# Transceivers.net
KiCad netlist of a schematic drawn in Altium Designer
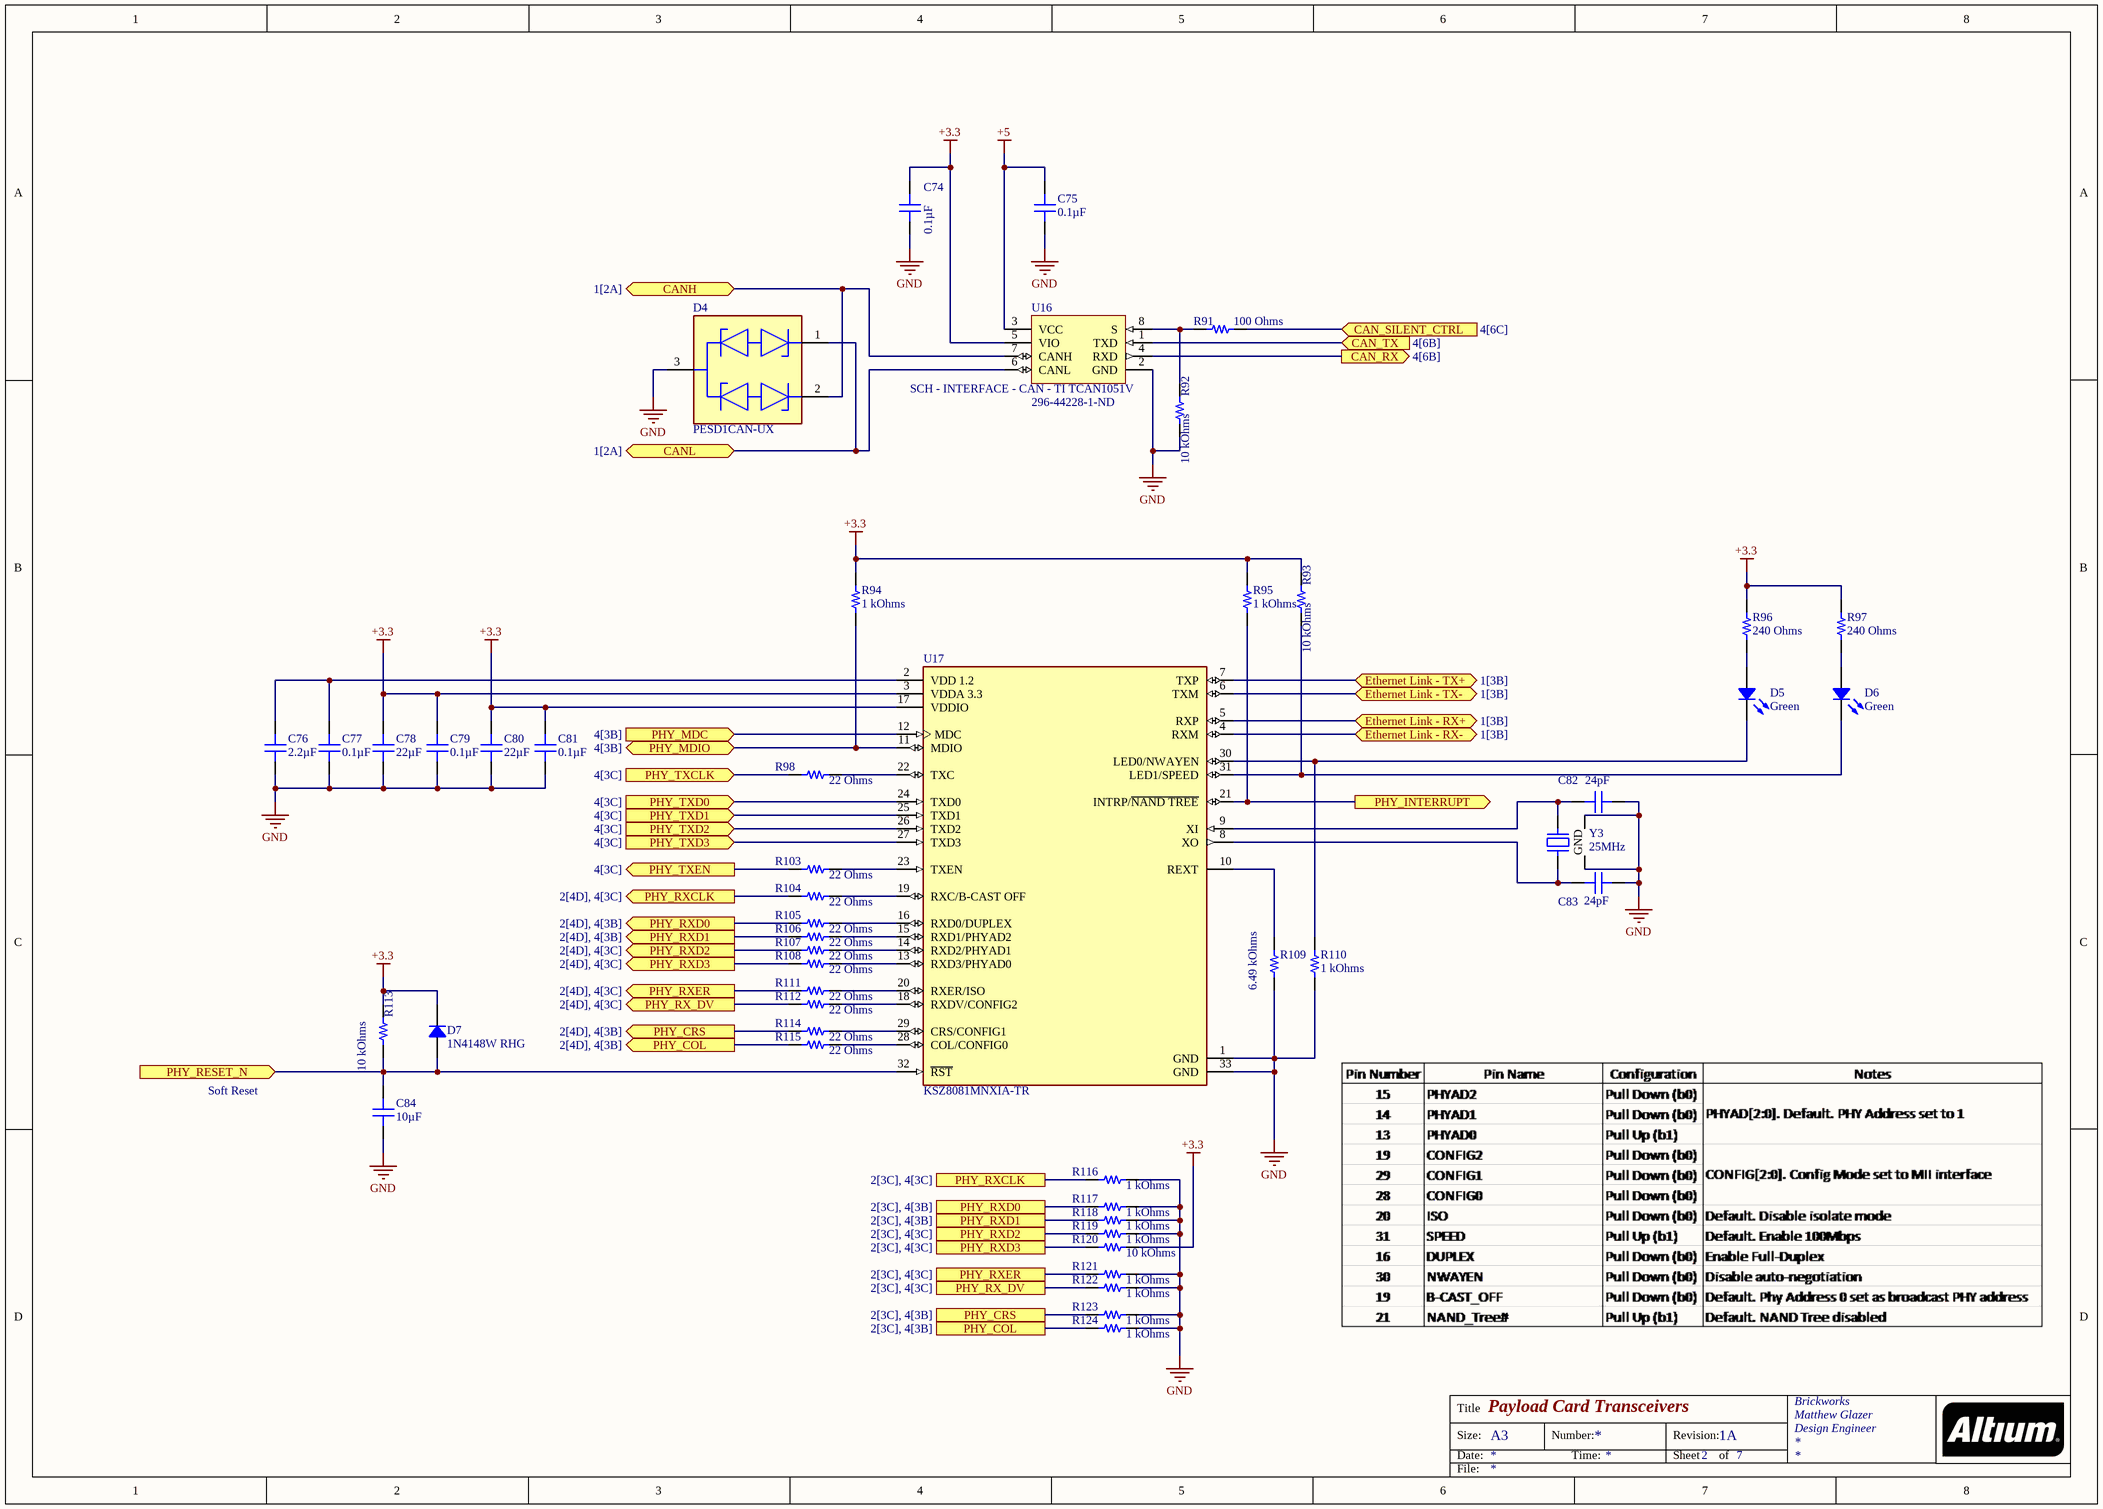
[diagram p0: Transceivers.SchDoc]

(export (version "E")
  (design (tool "Eeschema 10.0.6"))
  (components
    (comp (ref "C74")
      (value "0.1µF")
      (footprint "CAP 0603_1608")
      (description "CAP CER 0.1UF 25V X7R 0603")
      (fields
        (field (name "PART NUMBER") "CL10B104KA8WPNC")
        (field (name "MANUFACTURER") "Samsung Electro-Mechanics")
      )
      (libsource (lib "Celestial Altium Library - altium_library") (part "Capacitor"))
    )
    (comp (ref "C75")
      (value "0.1µF")
      (footprint "CAP 0603_1608")
      (description "CAP CER 0.1UF 25V X7R 0603")
      (fields
        (field (name "PART NUMBER") "CL10B104KA8WPNC")
        (field (name "MANUFACTURER") "Samsung Electro-Mechanics")
      )
      (libsource (lib "Celestial Altium Library - altium_library") (part "Capacitor"))
    )
    (comp (ref "C76")
      (value "2.2µF")
      (footprint "CAP 0805_2012")
      (description "CAP CER 2.2UF 10V X5R 0805")
      (fields
        (field (name "PART NUMBER") "CL21A225KPFNNNE")
        (field (name "MANUFACTURER") "Samsung Electro-Mechanics")
      )
      (libsource (lib "Celestial Altium Library - altium_library") (part "Capacitor"))
    )
    (comp (ref "C77")
      (value "0.1µF")
      (footprint "CAP 0603_1608")
      (description "CAP CER 0.1UF 25V X7R 0603")
      (fields
        (field (name "PART NUMBER") "CL10B104KA8WPNC")
        (field (name "MANUFACTURER") "Samsung Electro-Mechanics")
      )
      (libsource (lib "Celestial Altium Library - altium_library") (part "Capacitor"))
    )
    (comp (ref "C78")
      (value "22µF")
      (footprint "CAP 0805_2012")
      (description "CAP CER 22UF 10V X5R 0805")
      (fields
        (field (name "PART NUMBER") "CL21A226KPCLRNC")
        (field (name "MANUFACTURER") "Samsung Electro-Mechanics")
      )
      (libsource (lib "Celestial Altium Library - altium_library") (part "Capacitor"))
    )
    (comp (ref "C79")
      (value "0.1µF")
      (footprint "CAP 0603_1608")
      (description "CAP CER 0.1UF 25V X7R 0603")
      (fields
        (field (name "PART NUMBER") "CL10B104KA8WPNC")
        (field (name "MANUFACTURER") "Samsung Electro-Mechanics")
      )
      (libsource (lib "Celestial Altium Library - altium_library") (part "Capacitor"))
    )
    (comp (ref "C80")
      (value "22µF")
      (footprint "CAP 0805_2012")
      (description "CAP CER 22UF 10V X5R 0805")
      (fields
        (field (name "PART NUMBER") "CL21A226KPCLRNC")
        (field (name "MANUFACTURER") "Samsung Electro-Mechanics")
      )
      (libsource (lib "Celestial Altium Library - altium_library") (part "Capacitor"))
    )
    (comp (ref "C81")
      (value "0.1µF")
      (footprint "CAP 0603_1608")
      (description "CAP CER 0.1UF 25V X7R 0603")
      (fields
        (field (name "PART NUMBER") "CL10B104KA8WPNC")
        (field (name "MANUFACTURER") "Samsung Electro-Mechanics")
      )
      (libsource (lib "Celestial Altium Library - altium_library") (part "Capacitor"))
    )
    (comp (ref "C82")
      (value "24pF")
      (footprint "CAP 0603_1608")
      (description "CAP CER 24PF 50V C0G/NP0 0603")
      (fields
        (field (name "PART NUMBER") "CL10C240JB8NNNC")
        (field (name "MANUFACTURER") "Samsung Electro-Mechanics")
      )
      (libsource (lib "Celestial Altium Library - altium_library") (part "Capacitor"))
    )
    (comp (ref "C83")
      (value "24pF")
      (footprint "CAP 0603_1608")
      (description "CAP CER 24PF 50V C0G/NP0 0603")
      (fields
        (field (name "PART NUMBER") "CL10C240JB8NNNC")
        (field (name "MANUFACTURER") "Samsung Electro-Mechanics")
      )
      (libsource (lib "Celestial Altium Library - altium_library") (part "Capacitor"))
    )
    (comp (ref "C84")
      (value "10µF")
      (footprint "CAP 0805_2012")
      (description "CAP CER 10UF 16V X5R 0805")
      (fields (field (name "PART NUMBER") "CC0805KKX5R7BB106") (field (name "MANUFACTURER") "Yageo"))
      (libsource (lib "Celestial Altium Library - altium_library") (part "Capacitor"))
    )
    (comp (ref "D4")
      (value "PESD1CAN-UX")
      (footprint "FP-SOT323-MFG")
      (description "TVS DIODE 24V 50V SC70-3")
      (libsource (lib "Altium Content Vault") (part "04d57993b6b7b0f5b3c95ba4f97dea0"))
    )
    (comp (ref "D5")
      (value "Green")
      (footprint "LED 0603_1608 GREEN")
      (description "LED GREEN CLEAR CHIP SMD")
      (fields (field (name "PART NUMBER") "LTST-C193KGKT-5A") (field (name "MANUFACTURER") "Lite-On Inc."))
      (libsource (lib "Celestial Altium Library - altium_library") (part "LED"))
    )
    (comp (ref "D6")
      (value "Green")
      (footprint "LED 0603_1608 GREEN")
      (description "LED GREEN CLEAR CHIP SMD")
      (fields (field (name "PART NUMBER") "LTST-C193KGKT-5A") (field (name "MANUFACTURER") "Lite-On Inc."))
      (libsource (lib "Celestial Altium Library - altium_library") (part "LED"))
    )
    (comp (ref "D7")
      (value "1N4148W RHG")
      (footprint "SOD123F")
      (description "DIODE GEN PURP 100V 150MA SOD123")
      (fields (field (name "MANUFACTURER") "Taiwan Semiconductor Corporation"))
      (libsource (lib "Celestial Altium Library - altium_library") (part "Diode"))
    )
    (comp (ref "R91")
      (value "100 Ohms")
      (footprint "RES 0603_1608")
      (description "RES 100 OHM 1% 1/10W 0603")
      (fields
        (field (name "PART NUMBER") "RMCF0603FG100R")
        (field (name "MANUFACTURER") "Stackpole Electronics Inc")
      )
      (libsource (lib "Celestial Altium Library - altium_library") (part "Resistor"))
    )
    (comp (ref "R92")
      (value "10 kOhms")
      (footprint "RES 0603_1608")
      (description "RES 10K OHM 5% 1/10W 0603")
      (fields
        (field (name "PART NUMBER") "RMCF0603JT10K0")
        (field (name "MANUFACTURER") "Stackpole Electronics Inc")
      )
      (libsource (lib "Celestial Altium Library - altium_library") (part "Resistor"))
    )
    (comp (ref "R93")
      (value "10 kOhms")
      (footprint "RES 0603_1608")
      (description "RES 10K OHM 5% 1/10W 0603")
      (fields
        (field (name "PART NUMBER") "RMCF0603JT10K0")
        (field (name "MANUFACTURER") "Stackpole Electronics Inc")
      )
      (libsource (lib "Celestial Altium Library - altium_library") (part "Resistor"))
    )
    (comp (ref "R94")
      (value "1 kOhms")
      (footprint "RES 0603_1608")
      (description "RES 1K OHM 1% 1/8W 0603")
      (fields
        (field (name "PART NUMBER") "RNCP0603FTD1K00")
        (field (name "MANUFACTURER") "Stackpole Electronics Inc")
      )
      (libsource (lib "Celestial Altium Library - altium_library") (part "Resistor"))
    )
    (comp (ref "R95")
      (value "1 kOhms")
      (footprint "RES 0603_1608")
      (description "RES 1K OHM 1% 1/8W 0603")
      (fields
        (field (name "PART NUMBER") "RNCP0603FTD1K00")
        (field (name "MANUFACTURER") "Stackpole Electronics Inc")
      )
      (libsource (lib "Celestial Altium Library - altium_library") (part "Resistor"))
    )
    (comp (ref "R96")
      (value "240 Ohms")
      (footprint "RES 0603_1608")
      (description "RES 240 OHM 5% 1/10W 0603")
      (fields
        (field (name "PART NUMBER") "RMCF0603JT240R")
        (field (name "MANUFACTURER") "Stackpole Electronics Inc")
      )
      (libsource (lib "Celestial Altium Library - altium_library") (part "Resistor"))
    )
    (comp (ref "R97")
      (value "240 Ohms")
      (footprint "RES 0603_1608")
      (description "RES 240 OHM 5% 1/10W 0603")
      (fields
        (field (name "PART NUMBER") "RMCF0603JT240R")
        (field (name "MANUFACTURER") "Stackpole Electronics Inc")
      )
      (libsource (lib "Celestial Altium Library - altium_library") (part "Resistor"))
    )
    (comp (ref "R98")
      (value "22 Ohms")
      (footprint "RES 0603_1608")
      (description "RES 22 OHM 1% 1/10W 0603")
      (fields
        (field (name "PART NUMBER") "RMCF0603FT22R0")
        (field (name "MANUFACTURER") "Stackpole Electronics Inc")
      )
      (libsource (lib "Celestial Altium Library - altium_library") (part "Resistor"))
    )
    (comp (ref "R103")
      (value "22 Ohms")
      (footprint "RES 0603_1608")
      (description "RES 22 OHM 1% 1/10W 0603")
      (fields
        (field (name "PART NUMBER") "RMCF0603FT22R0")
        (field (name "MANUFACTURER") "Stackpole Electronics Inc")
      )
      (libsource (lib "Celestial Altium Library - altium_library") (part "Resistor"))
    )
    (comp (ref "R104")
      (value "22 Ohms")
      (footprint "RES 0603_1608")
      (description "RES 22 OHM 1% 1/10W 0603")
      (fields
        (field (name "PART NUMBER") "RMCF0603FT22R0")
        (field (name "MANUFACTURER") "Stackpole Electronics Inc")
      )
      (libsource (lib "Celestial Altium Library - altium_library") (part "Resistor"))
    )
    (comp (ref "R105")
      (value "22 Ohms")
      (footprint "RES 0603_1608")
      (description "RES 22 OHM 1% 1/10W 0603")
      (fields
        (field (name "PART NUMBER") "RMCF0603FT22R0")
        (field (name "MANUFACTURER") "Stackpole Electronics Inc")
      )
      (libsource (lib "Celestial Altium Library - altium_library") (part "Resistor"))
    )
    (comp (ref "R106")
      (value "22 Ohms")
      (footprint "RES 0603_1608")
      (description "RES 22 OHM 1% 1/10W 0603")
      (fields
        (field (name "PART NUMBER") "RMCF0603FT22R0")
        (field (name "MANUFACTURER") "Stackpole Electronics Inc")
      )
      (libsource (lib "Celestial Altium Library - altium_library") (part "Resistor"))
    )
    (comp (ref "R107")
      (value "22 Ohms")
      (footprint "RES 0603_1608")
      (description "RES 22 OHM 1% 1/10W 0603")
      (fields
        (field (name "PART NUMBER") "RMCF0603FT22R0")
        (field (name "MANUFACTURER") "Stackpole Electronics Inc")
      )
      (libsource (lib "Celestial Altium Library - altium_library") (part "Resistor"))
    )
    (comp (ref "R108")
      (value "22 Ohms")
      (footprint "RES 0603_1608")
      (description "RES 22 OHM 1% 1/10W 0603")
      (fields
        (field (name "PART NUMBER") "RMCF0603FT22R0")
        (field (name "MANUFACTURER") "Stackpole Electronics Inc")
      )
      (libsource (lib "Celestial Altium Library - altium_library") (part "Resistor"))
    )
    (comp (ref "R109")
      (value "6.49 kOhms")
      (footprint "RES 0603_1608")
      (description "RES 6.49K OHM 1% 1/8W 0603")
      (fields
        (field (name "PART NUMBER") "RNCP0603FTD6K49")
        (field (name "MANUFACTURER") "Stackpole Electronics Inc")
      )
      (libsource (lib "Celestial Altium Library - altium_library") (part "Resistor"))
    )
    (comp (ref "R110")
      (value "1 kOhms")
      (footprint "RES 0603_1608")
      (description "RES 1K OHM 1% 1/8W 0603")
      (fields
        (field (name "PART NUMBER") "RNCP0603FTD1K00")
        (field (name "MANUFACTURER") "Stackpole Electronics Inc")
      )
      (libsource (lib "Celestial Altium Library - altium_library") (part "Resistor"))
    )
    (comp (ref "R111")
      (value "22 Ohms")
      (footprint "RES 0603_1608")
      (description "RES 22 OHM 1% 1/10W 0603")
      (fields
        (field (name "PART NUMBER") "RMCF0603FT22R0")
        (field (name "MANUFACTURER") "Stackpole Electronics Inc")
      )
      (libsource (lib "Celestial Altium Library - altium_library") (part "Resistor"))
    )
    (comp (ref "R112")
      (value "22 Ohms")
      (footprint "RES 0603_1608")
      (description "RES 22 OHM 1% 1/10W 0603")
      (fields
        (field (name "PART NUMBER") "RMCF0603FT22R0")
        (field (name "MANUFACTURER") "Stackpole Electronics Inc")
      )
      (libsource (lib "Celestial Altium Library - altium_library") (part "Resistor"))
    )
    (comp (ref "R113")
      (value "10 kOhms")
      (footprint "RES 0603_1608")
      (description "RES 10K OHM 5% 1/10W 0603")
      (fields
        (field (name "PART NUMBER") "RMCF0603JT10K0")
        (field (name "MANUFACTURER") "Stackpole Electronics Inc")
      )
      (libsource (lib "Celestial Altium Library - altium_library") (part "Resistor"))
    )
    (comp (ref "R114")
      (value "22 Ohms")
      (footprint "RES 0603_1608")
      (description "RES 22 OHM 1% 1/10W 0603")
      (fields
        (field (name "PART NUMBER") "RMCF0603FT22R0")
        (field (name "MANUFACTURER") "Stackpole Electronics Inc")
      )
      (libsource (lib "Celestial Altium Library - altium_library") (part "Resistor"))
    )
    (comp (ref "R115")
      (value "22 Ohms")
      (footprint "RES 0603_1608")
      (description "RES 22 OHM 1% 1/10W 0603")
      (fields
        (field (name "PART NUMBER") "RMCF0603FT22R0")
        (field (name "MANUFACTURER") "Stackpole Electronics Inc")
      )
      (libsource (lib "Celestial Altium Library - altium_library") (part "Resistor"))
    )
    (comp (ref "R116")
      (value "1 kOhms")
      (footprint "RES 0603_1608")
      (description "RES 1K OHM 1% 1/8W 0603")
      (fields
        (field (name "PART NUMBER") "RNCP0603FTD1K00")
        (field (name "MANUFACTURER") "Stackpole Electronics Inc")
      )
      (libsource (lib "Celestial Altium Library - altium_library") (part "Resistor"))
    )
    (comp (ref "R117")
      (value "1 kOhms")
      (footprint "RES 0603_1608")
      (description "RES 1K OHM 1% 1/8W 0603")
      (fields
        (field (name "PART NUMBER") "RNCP0603FTD1K00")
        (field (name "MANUFACTURER") "Stackpole Electronics Inc")
      )
      (libsource (lib "Celestial Altium Library - altium_library") (part "Resistor"))
    )
    (comp (ref "R118")
      (value "1 kOhms")
      (footprint "RES 0603_1608")
      (description "RES 1K OHM 1% 1/8W 0603")
      (fields
        (field (name "PART NUMBER") "RNCP0603FTD1K00")
        (field (name "MANUFACTURER") "Stackpole Electronics Inc")
      )
      (libsource (lib "Celestial Altium Library - altium_library") (part "Resistor"))
    )
    (comp (ref "R119")
      (value "1 kOhms")
      (footprint "RES 0603_1608")
      (description "RES 1K OHM 1% 1/8W 0603")
      (fields
        (field (name "PART NUMBER") "RNCP0603FTD1K00")
        (field (name "MANUFACTURER") "Stackpole Electronics Inc")
      )
      (libsource (lib "Celestial Altium Library - altium_library") (part "Resistor"))
    )
    (comp (ref "R120")
      (value "10 kOhms")
      (footprint "RES 0603_1608")
      (description "RES 10K OHM 5% 1/10W 0603")
      (fields
        (field (name "PART NUMBER") "RMCF0603JT10K0")
        (field (name "MANUFACTURER") "Stackpole Electronics Inc")
      )
      (libsource (lib "Celestial Altium Library - altium_library") (part "Resistor"))
    )
    (comp (ref "R121")
      (value "1 kOhms")
      (footprint "RES 0603_1608")
      (description "RES 1K OHM 1% 1/8W 0603")
      (fields
        (field (name "PART NUMBER") "RNCP0603FTD1K00")
        (field (name "MANUFACTURER") "Stackpole Electronics Inc")
      )
      (libsource (lib "Celestial Altium Library - altium_library") (part "Resistor"))
    )
    (comp (ref "R122")
      (value "1 kOhms")
      (footprint "RES 0603_1608")
      (description "RES 1K OHM 1% 1/8W 0603")
      (fields
        (field (name "PART NUMBER") "RNCP0603FTD1K00")
        (field (name "MANUFACTURER") "Stackpole Electronics Inc")
      )
      (libsource (lib "Celestial Altium Library - altium_library") (part "Resistor"))
    )
    (comp (ref "R123")
      (value "1 kOhms")
      (footprint "RES 0603_1608")
      (description "RES 1K OHM 1% 1/8W 0603")
      (fields
        (field (name "PART NUMBER") "RNCP0603FTD1K00")
        (field (name "MANUFACTURER") "Stackpole Electronics Inc")
      )
      (libsource (lib "Celestial Altium Library - altium_library") (part "Resistor"))
    )
    (comp (ref "R124")
      (value "1 kOhms")
      (footprint "RES 0603_1608")
      (description "RES 1K OHM 1% 1/8W 0603")
      (fields
        (field (name "PART NUMBER") "RNCP0603FTD1K00")
        (field (name "MANUFACTURER") "Stackpole Electronics Inc")
      )
      (libsource (lib "Celestial Altium Library - altium_library") (part "Resistor"))
    )
    (comp (ref "U16")
      (value "SCH - INTERFACE - CAN - TI TCAN1051V")
      (footprint "PCB - LEADS - SOIC - TI SOIC-8")
      (fields (field (name "SUPPLIER PART NUMBER 1") "296-44228-1-ND"))
      (libsource (lib "HAB_ICs") (part "SCH - INTERFACE - CAN - TI TCAN1051V"))
    )
    (comp (ref "U17")
      (value "KSZ8081MNXIA-TR")
      (footprint "FP-QFN55-32LD-PL-5-MFG")
      (description "IC TRANSCEIVER FULL 1/1 32QFN")
      (fields
        (field (name "OCTOPART") "https://octopart.com/ksz8081mnxia-tr-microchip-66799958")
        (field (name "MANUFACTURER") "Microchip")
      )
      (libsource (lib "Altium Content Vault") (part "882547a6550c82911a23300368c51e3"))
    )
    (comp (ref "Y3")
      (value "25MHz")
      (footprint "EPSON TSX-3225")
      (description "CRYSTAL 25.0000MHZ 18PF SMD")
      (fields (field (name "PART NUMBER") "TSX-3225 25.0000MF20P-C0") (field (name "MANUFACTURER") "EPSON"))
      (libsource (lib "Celestial Altium Library - altium_library") (part "Epson Crystal TSX-3225"))
    )
  )
  (nets
    (net (code "1") (name "+3.3") (class "Default")
      (node (ref "C74") (pin "2") (pinfunction "2_2") (pintype "passive"))
      (node (ref "C78") (pin "2") (pinfunction "2_2") (pintype "passive"))
      (node (ref "C79") (pin "2") (pinfunction "2_2") (pintype "passive"))
      (node (ref "C80") (pin "2") (pinfunction "2_2") (pintype "passive"))
      (node (ref "C81") (pin "2") (pinfunction "2_2") (pintype "passive"))
      (node (ref "D7") (pin "2") (pinfunction "2_2") (pintype "passive"))
      (node (ref "R113") (pin "2") (pinfunction "2_2") (pintype "passive"))
      (node (ref "R120") (pin "1") (pinfunction "1_1") (pintype "passive"))
      (node (ref "R93") (pin "2") (pinfunction "2_2") (pintype "passive"))
      (node (ref "R94") (pin "2") (pinfunction "2_2") (pintype "passive"))
      (node (ref "R95") (pin "2") (pinfunction "2_2") (pintype "passive"))
      (node (ref "R96") (pin "2") (pinfunction "2_2") (pintype "passive"))
      (node (ref "R97") (pin "2") (pinfunction "2_2") (pintype "passive"))
      (node (ref "U16") (pin "5") (pinfunction "VIO_5") (pintype "power_in"))
      (node (ref "U17") (pin "17") (pinfunction "VDDIO_17") (pintype "power_in"))
      (node (ref "U17") (pin "3") (pinfunction "VDDA_3.3_3") (pintype "power_in"))
    )
    (net (code "2") (name "+5") (class "Default")
      (node (ref "C75") (pin "2") (pinfunction "2_2") (pintype "passive"))
      (node (ref "U16") (pin "3") (pinfunction "VCC_3") (pintype "power_in"))
    )
    (net (code "3") (name "/CANH") (class "Default")
      (node (ref "D4") (pin "2") (pinfunction "cathode_2_2") (pintype "passive"))
      (node (ref "U16") (pin "7") (pinfunction "CANH_7") (pintype "bidirectional"))
    )
    (net (code "4") (name "/CANL") (class "Default")
      (node (ref "D4") (pin "1") (pinfunction "cathode_1_1") (pintype "passive"))
      (node (ref "U16") (pin "6") (pinfunction "CANL_6") (pintype "bidirectional"))
    )
    (net (code "5") (name "/CAN_RX") (class "Default")
      (node (ref "U16") (pin "4") (pinfunction "RXD_4") (pintype "output"))
    )
    (net (code "6") (name "/CAN_SILENT_CTRL") (class "Default")
      (node (ref "R91") (pin "2") (pinfunction "2_2") (pintype "passive"))
    )
    (net (code "7") (name "/CAN_TX") (class "Default")
      (node (ref "U16") (pin "1") (pinfunction "TXD_1") (pintype "input"))
    )
    (net (code "8") (name "/Ethernet Link - RX+") (class "Default")
      (node (ref "U17") (pin "5") (pinfunction "RXP_5") (pintype "bidirectional"))
    )
    (net (code "9") (name "/Ethernet Link - RX-") (class "Default")
      (node (ref "U17") (pin "4") (pinfunction "RXM_4") (pintype "bidirectional"))
    )
    (net (code "10") (name "/Ethernet Link - TX+") (class "Default")
      (node (ref "U17") (pin "7") (pinfunction "TXP_7") (pintype "bidirectional"))
    )
    (net (code "11") (name "/Ethernet Link - TX-") (class "Default")
      (node (ref "U17") (pin "6") (pinfunction "TXM_6") (pintype "bidirectional"))
    )
    (net (code "12") (name "/PHY_COL") (class "Default")
      (node (ref "R115") (pin "1") (pinfunction "1_1") (pintype "passive"))
      (node (ref "R124") (pin "2") (pinfunction "2_2") (pintype "passive"))
    )
    (net (code "13") (name "/PHY_CRS") (class "Default")
      (node (ref "R114") (pin "1") (pinfunction "1_1") (pintype "passive"))
      (node (ref "R123") (pin "2") (pinfunction "2_2") (pintype "passive"))
    )
    (net (code "14") (name "/PHY_INTERRUPT") (class "Default")
      (node (ref "R95") (pin "1") (pinfunction "1_1") (pintype "passive"))
      (node (ref "U17") (pin "21") (pinfunction "INTRP/~{NAND_TREE}_21") (pintype "bidirectional"))
    )
    (net (code "15") (name "/PHY_MDC") (class "Default")
      (node (ref "U17") (pin "12") (pinfunction "MDC_12") (pintype "input"))
    )
    (net (code "16") (name "/PHY_MDIO") (class "Default")
      (node (ref "R94") (pin "1") (pinfunction "1_1") (pintype "passive"))
      (node (ref "U17") (pin "11") (pinfunction "MDIO_11") (pintype "bidirectional"))
    )
    (net (code "17") (name "/PHY_RESET_N") (class "Default")
      (node (ref "C84") (pin "2") (pinfunction "2_2") (pintype "passive"))
      (node (ref "D7") (pin "1") (pinfunction "1_1") (pintype "passive"))
      (node (ref "R113") (pin "1") (pinfunction "1_1") (pintype "passive"))
      (node (ref "U17") (pin "32") (pinfunction "~{RST}_32") (pintype "input"))
    )
    (net (code "18") (name "/PHY_RXCLK") (class "Default")
      (node (ref "R104") (pin "1") (pinfunction "1_1") (pintype "passive"))
      (node (ref "R116") (pin "2") (pinfunction "2_2") (pintype "passive"))
    )
    (net (code "19") (name "/PHY_RXD0") (class "Default")
      (node (ref "R105") (pin "1") (pinfunction "1_1") (pintype "passive"))
      (node (ref "R117") (pin "2") (pinfunction "2_2") (pintype "passive"))
    )
    (net (code "20") (name "/PHY_RXD1") (class "Default")
      (node (ref "R106") (pin "1") (pinfunction "1_1") (pintype "passive"))
      (node (ref "R118") (pin "2") (pinfunction "2_2") (pintype "passive"))
    )
    (net (code "21") (name "/PHY_RXD2") (class "Default")
      (node (ref "R107") (pin "1") (pinfunction "1_1") (pintype "passive"))
      (node (ref "R119") (pin "2") (pinfunction "2_2") (pintype "passive"))
    )
    (net (code "22") (name "/PHY_RXD3") (class "Default")
      (node (ref "R108") (pin "1") (pinfunction "1_1") (pintype "passive"))
      (node (ref "R120") (pin "2") (pinfunction "2_2") (pintype "passive"))
    )
    (net (code "23") (name "/PHY_RXER") (class "Default")
      (node (ref "R111") (pin "1") (pinfunction "1_1") (pintype "passive"))
      (node (ref "R121") (pin "2") (pinfunction "2_2") (pintype "passive"))
    )
    (net (code "24") (name "/PHY_RX_DV") (class "Default")
      (node (ref "R112") (pin "1") (pinfunction "1_1") (pintype "passive"))
      (node (ref "R122") (pin "2") (pinfunction "2_2") (pintype "passive"))
    )
    (net (code "25") (name "/PHY_TXCLK") (class "Default")
      (node (ref "R98") (pin "1") (pinfunction "1_1") (pintype "passive"))
    )
    (net (code "26") (name "/PHY_TXD0") (class "Default")
      (node (ref "U17") (pin "24") (pinfunction "TXD0_24") (pintype "input"))
    )
    (net (code "27") (name "/PHY_TXD1") (class "Default")
      (node (ref "U17") (pin "25") (pinfunction "TXD1_25") (pintype "input"))
    )
    (net (code "28") (name "/PHY_TXD2") (class "Default")
      (node (ref "U17") (pin "26") (pinfunction "TXD2_26") (pintype "input"))
    )
    (net (code "29") (name "/PHY_TXD3") (class "Default")
      (node (ref "U17") (pin "27") (pinfunction "TXD3_27") (pintype "input"))
    )
    (net (code "30") (name "/PHY_TXEN") (class "Default")
      (node (ref "R103") (pin "1") (pinfunction "1_1") (pintype "passive"))
    )
    (net (code "31") (name "GND") (class "Default")
      (node (ref "C74") (pin "1") (pinfunction "1_1") (pintype "passive"))
      (node (ref "C75") (pin "1") (pinfunction "1_1") (pintype "passive"))
      (node (ref "C76") (pin "1") (pinfunction "1_1") (pintype "passive"))
      (node (ref "C77") (pin "1") (pinfunction "1_1") (pintype "passive"))
      (node (ref "C78") (pin "1") (pinfunction "1_1") (pintype "passive"))
      (node (ref "C79") (pin "1") (pinfunction "1_1") (pintype "passive"))
      (node (ref "C80") (pin "1") (pinfunction "1_1") (pintype "passive"))
      (node (ref "C81") (pin "1") (pinfunction "1_1") (pintype "passive"))
      (node (ref "C82") (pin "2") (pinfunction "2_2") (pintype "passive"))
      (node (ref "C83") (pin "2") (pinfunction "2_2") (pintype "passive"))
      (node (ref "C84") (pin "1") (pinfunction "1_1") (pintype "passive"))
      (node (ref "D4") (pin "3") (pinfunction "common_cathode_3") (pintype "passive"))
      (node (ref "R109") (pin "1") (pinfunction "1_1") (pintype "passive"))
      (node (ref "R110") (pin "1") (pinfunction "1_1") (pintype "passive"))
      (node (ref "R116") (pin "1") (pinfunction "1_1") (pintype "passive"))
      (node (ref "R117") (pin "1") (pinfunction "1_1") (pintype "passive"))
      (node (ref "R118") (pin "1") (pinfunction "1_1") (pintype "passive"))
      (node (ref "R119") (pin "1") (pinfunction "1_1") (pintype "passive"))
      (node (ref "R121") (pin "1") (pinfunction "1_1") (pintype "passive"))
      (node (ref "R122") (pin "1") (pinfunction "1_1") (pintype "passive"))
      (node (ref "R123") (pin "1") (pinfunction "1_1") (pintype "passive"))
      (node (ref "R124") (pin "1") (pinfunction "1_1") (pintype "passive"))
      (node (ref "R92") (pin "1") (pinfunction "1_1") (pintype "passive"))
      (node (ref "U16") (pin "2") (pinfunction "GND_2") (pintype "power_in"))
      (node (ref "U17") (pin "1") (pinfunction "GND_1") (pintype "power_in"))
      (node (ref "U17") (pin "33") (pinfunction "GND_33") (pintype "power_in"))
      (node (ref "Y3") (pin "2") (pinfunction "GND_2") (pintype "passive"))
      (node (ref "Y3") (pin "4") (pinfunction "GND_4") (pintype "passive"))
    )
    (net (code "32") (name "Net-(D5-Pad1)") (class "Default")
      (node (ref "D5") (pin "1") (pinfunction "1_1") (pintype "passive"))
      (node (ref "R96") (pin "1") (pinfunction "1_1") (pintype "passive"))
    )
    (net (code "33") (name "Net-(D6-Pad1)") (class "Default")
      (node (ref "D6") (pin "1") (pinfunction "1_1") (pintype "passive"))
      (node (ref "R97") (pin "1") (pinfunction "1_1") (pintype "passive"))
    )
    (net (code "34") (name "Net-(U16-S)") (class "Default")
      (node (ref "R91") (pin "1") (pinfunction "1_1") (pintype "passive"))
      (node (ref "R92") (pin "2") (pinfunction "2_2") (pintype "passive"))
      (node (ref "U16") (pin "8") (pinfunction "S_8") (pintype "input"))
    )
    (net (code "35") (name "Net-(U17-COL{slash}CONFIG0)") (class "Default")
      (node (ref "R115") (pin "2") (pinfunction "2_2") (pintype "passive"))
      (node (ref "U17") (pin "28") (pinfunction "COL/CONFIG0_28") (pintype "bidirectional"))
    )
    (net (code "36") (name "Net-(U17-CRS{slash}CONFIG1)") (class "Default")
      (node (ref "R114") (pin "2") (pinfunction "2_2") (pintype "passive"))
      (node (ref "U17") (pin "29") (pinfunction "CRS/CONFIG1_29") (pintype "bidirectional"))
    )
    (net (code "37") (name "Net-(U17-LED0{slash}NWAYEN)") (class "Default")
      (node (ref "D5") (pin "2") (pinfunction "2_2") (pintype "passive"))
      (node (ref "R110") (pin "2") (pinfunction "2_2") (pintype "passive"))
      (node (ref "U17") (pin "30") (pinfunction "LED0/NWAYEN_30") (pintype "bidirectional"))
    )
    (net (code "38") (name "Net-(U17-LED1{slash}SPEED)") (class "Default")
      (node (ref "D6") (pin "2") (pinfunction "2_2") (pintype "passive"))
      (node (ref "R93") (pin "1") (pinfunction "1_1") (pintype "passive"))
      (node (ref "U17") (pin "31") (pinfunction "LED1/SPEED_31") (pintype "bidirectional"))
    )
    (net (code "39") (name "Net-(U17-REXT)") (class "Default")
      (node (ref "R109") (pin "2") (pinfunction "2_2") (pintype "passive"))
      (node (ref "U17") (pin "10") (pinfunction "REXT_10") (pintype "passive"))
    )
    (net (code "40") (name "Net-(U17-RXC{slash}B-CAST_OFF)") (class "Default")
      (node (ref "R104") (pin "2") (pinfunction "2_2") (pintype "passive"))
      (node (ref "U17") (pin "19") (pinfunction "RXC/B-CAST_OFF_19") (pintype "bidirectional"))
    )
    (net (code "41") (name "Net-(U17-RXD0{slash}DUPLEX)") (class "Default")
      (node (ref "R105") (pin "2") (pinfunction "2_2") (pintype "passive"))
      (node (ref "U17") (pin "16") (pinfunction "RXD0/DUPLEX_16") (pintype "bidirectional"))
    )
    (net (code "42") (name "Net-(U17-RXD1{slash}PHYAD2)") (class "Default")
      (node (ref "R106") (pin "2") (pinfunction "2_2") (pintype "passive"))
      (node (ref "U17") (pin "15") (pinfunction "RXD1/PHYAD2_15") (pintype "bidirectional"))
    )
    (net (code "43") (name "Net-(U17-RXD2{slash}PHYAD1)") (class "Default")
      (node (ref "R107") (pin "2") (pinfunction "2_2") (pintype "passive"))
      (node (ref "U17") (pin "14") (pinfunction "RXD2/PHYAD1_14") (pintype "bidirectional"))
    )
    (net (code "44") (name "Net-(U17-RXD3{slash}PHYAD0)") (class "Default")
      (node (ref "R108") (pin "2") (pinfunction "2_2") (pintype "passive"))
      (node (ref "U17") (pin "13") (pinfunction "RXD3/PHYAD0_13") (pintype "bidirectional"))
    )
    (net (code "45") (name "Net-(U17-RXDV{slash}CONFIG2)") (class "Default")
      (node (ref "R112") (pin "2") (pinfunction "2_2") (pintype "passive"))
      (node (ref "U17") (pin "18") (pinfunction "RXDV/CONFIG2_18") (pintype "bidirectional"))
    )
    (net (code "46") (name "Net-(U17-RXER{slash}ISO)") (class "Default")
      (node (ref "R111") (pin "2") (pinfunction "2_2") (pintype "passive"))
      (node (ref "U17") (pin "20") (pinfunction "RXER/ISO_20") (pintype "bidirectional"))
    )
    (net (code "47") (name "Net-(U17-TXC)") (class "Default")
      (node (ref "R98") (pin "2") (pinfunction "2_2") (pintype "passive"))
      (node (ref "U17") (pin "22") (pinfunction "TXC_22") (pintype "bidirectional"))
    )
    (net (code "48") (name "Net-(U17-TXEN)") (class "Default")
      (node (ref "R103") (pin "2") (pinfunction "2_2") (pintype "passive"))
      (node (ref "U17") (pin "23") (pinfunction "TXEN_23") (pintype "input"))
    )
    (net (code "49") (name "Net-(U17-VDD_1.2)") (class "Default")
      (node (ref "C76") (pin "2") (pinfunction "2_2") (pintype "passive"))
      (node (ref "C77") (pin "2") (pinfunction "2_2") (pintype "passive"))
      (node (ref "U17") (pin "2") (pinfunction "VDD_1.2_2") (pintype "power_in"))
    )
    (net (code "50") (name "Net-(U17-XI)") (class "Default")
      (node (ref "C82") (pin "1") (pinfunction "1_1") (pintype "passive"))
      (node (ref "U17") (pin "9") (pinfunction "XI_9") (pintype "input"))
      (node (ref "Y3") (pin "3") (pinfunction "3_3") (pintype "passive"))
    )
    (net (code "51") (name "Net-(U17-XO)") (class "Default")
      (node (ref "C83") (pin "1") (pinfunction "1_1") (pintype "passive"))
      (node (ref "U17") (pin "8") (pinfunction "XO_8") (pintype "output"))
      (node (ref "Y3") (pin "1") (pinfunction "1_1") (pintype "passive"))
    )
  )
)
